# openSX70_LENS_BELLOWS_V5_5-SEEED_2018051.net
KiCad netlist of a schematic drawn in EAGLE
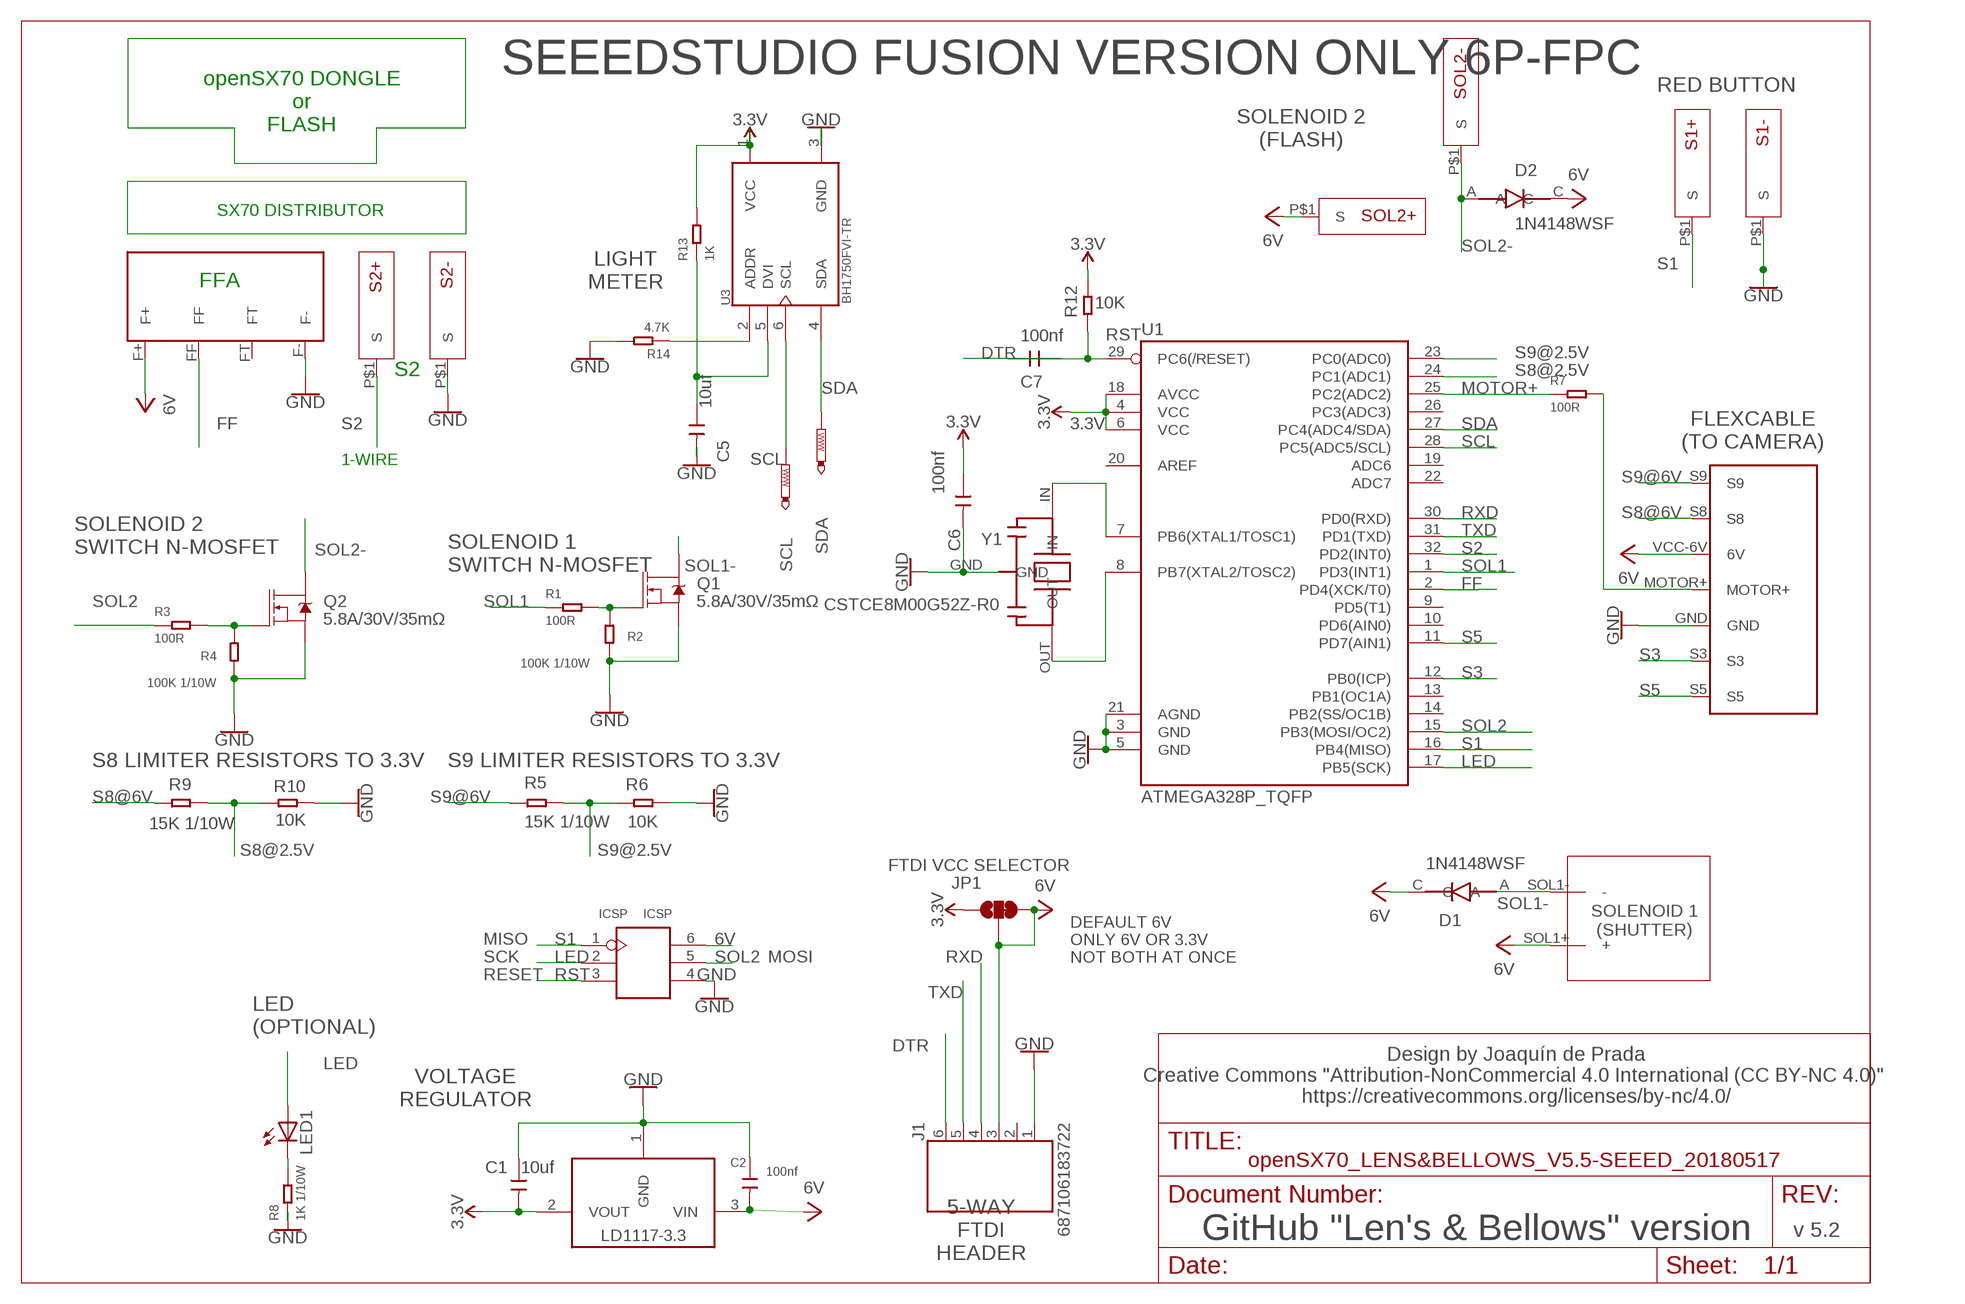
[diagram p0: schematic, sheet 1]

(export (version "E")
  (design (tool "Eeschema 10.0.6"))
  (components
    (comp (ref "C1")
      (value "10uf")
      (footprint "eagle-import:C0603")
      (fields (field (name "MPN") "CC0603KRX5R6BB106"))
      (libsource (lib "eagle-import") (part "CERAMIC-10UF-10V-10%-X5R(0603)"))
    )
    (comp (ref "C2")
      (value "100nf")
      (footprint "eagle-import:C0603")
      (fields (field (name "MPN") "CC0603KRX7R9BB104"))
      (libsource (lib "eagle-import") (part "CERAMIC-100NF-50V-10%-X7R(0603)"))
    )
    (comp (ref "C5")
      (value "10uf")
      (footprint "eagle-import:C0603")
      (fields (field (name "MPN") "CC0603KRX5R6BB106"))
      (libsource (lib "eagle-import") (part "CERAMIC-10UF-10V-10%-X5R(0603)"))
    )
    (comp (ref "C6")
      (value "100nf")
      (footprint "eagle-import:C0603")
      (fields (field (name "MPN") "CC0603KRX7R9BB104"))
      (libsource (lib "eagle-import") (part "CERAMIC-100NF-50V-10%-X7R(0603)"))
    )
    (comp (ref "C7")
      (value "100nf")
      (footprint "eagle-import:C0603")
      (fields (field (name "MPN") "CC0603KRX7R9BB104"))
      (libsource (lib "eagle-import") (part "CERAMIC-100NF-50V-10%-X7R(0603)"))
    )
    (comp (ref "D1")
      (value "1N4148WSF")
      (footprint "eagle-import:SODFL2512X100N")
      (fields (field (name "MANUFACTURER") "Fairchild Semiconductor"))
      (libsource (lib "eagle-import") (part "1N4148WS"))
    )
    (comp (ref "D2")
      (value "1N4148WSF")
      (footprint "eagle-import:SODFL2512X100N")
      (fields (field (name "MANUFACTURER") "Fairchild Semiconductor"))
      (libsource (lib "eagle-import") (part "1N4148WS"))
    )
    (comp (ref "ICSP")
      (value "ICSP")
      (footprint "eagle-import:H2X3-2.54")
      (libsource (lib "eagle-import") (part "ICSP"))
    )
    (comp (ref "J1")
      (value "687106183722")
      (footprint "eagle-import:687106183722")
      (fields (field (name "MF") "Wurth Electronics"))
      (libsource (lib "eagle-import") (part "687106183722"))
    )
    (comp (ref "JP1")
      (value "FTDI VCC SELECTOR")
      (footprint "eagle-import:SMT-JUMPER_3_1-NC_TRACE_SILK")
      (libsource (lib "eagle-import") (part "JUMPER-SMT_3_1-NC_TRACE_SILK"))
    )
    (comp (ref "LD11172.5V")
      (value "LD1117 2.5V")
      (footprint "eagle-import:SOT223")
      (fields (field (name "MF") "Advanced Monolithic Systems") (field (name "MP") "AMS1117-5.0"))
      (libsource (lib "eagle-import") (part "LD1117-3.3"))
    )
    (comp (ref "LED1")
      (value "LEDCHIPLED_0805")
      (footprint "eagle-import:CHIPLED_0805")
      (libsource (lib "eagle-import") (part "LEDCHIPLED_0805"))
    )
    (comp (ref "Q1")
      (value "5.8A/30V/35mΩ")
      (footprint "eagle-import:SOT23-3")
      (libsource (lib "eagle-import") (part "MOSFET-NCH-AO3404A"))
    )
    (comp (ref "Q2")
      (value "5.8A/30V/35mΩ")
      (footprint "eagle-import:SOT23-3")
      (libsource (lib "eagle-import") (part "MOSFET-NCH-AO3404A"))
    )
    (comp (ref "R1")
      (value "100R")
      (footprint "eagle-import:R0603")
      (fields (field (name "MPN") "RC0603JR-07100RL"))
      (libsource (lib "eagle-import") (part "SMD-RES-100R-5%-1/10W(0603)"))
    )
    (comp (ref "R2")
      (value "100K 1/10W")
      (footprint "eagle-import:R0603")
      (fields (field (name "MPN") "RC0603JR-07100KL"))
      (libsource (lib "eagle-import") (part "SMD-RES-100K-5%-1/10W(0603)"))
    )
    (comp (ref "R3")
      (value "100R")
      (footprint "eagle-import:R0603")
      (fields (field (name "MPN") "RC0603JR-07100RL"))
      (libsource (lib "eagle-import") (part "SMD-RES-100R-5%-1/10W(0603)"))
    )
    (comp (ref "R4")
      (value "100K 1/10W")
      (footprint "eagle-import:R0603")
      (fields (field (name "MPN") "RC0603JR-07100KL"))
      (libsource (lib "eagle-import") (part "SMD-RES-100K-5%-1/10W(0603)"))
    )
    (comp (ref "R5")
      (value "15K 1/10W")
      (footprint "eagle-import:R0603")
      (fields (field (name "MPN") "RC0603FR-0715KL"))
      (libsource (lib "eagle-import") (part "SMD-RES-15K-1%-1/10W(0603)"))
    )
    (comp (ref "R6")
      (value "10K")
      (footprint "eagle-import:R0603")
      (fields (field (name "MPN") "RC0603FR-0710KL"))
      (libsource (lib "eagle-import") (part "SMD-RES-10K-1%-1/10W(0603)"))
    )
    (comp (ref "R7")
      (value "100R")
      (footprint "eagle-import:R0603")
      (fields (field (name "MPN") "RC0603JR-07100RL"))
      (libsource (lib "eagle-import") (part "SMD-RES-100R-5%-1/10W(0603)"))
    )
    (comp (ref "R8")
      (value "1K 1/10W")
      (footprint "eagle-import:R0603")
      (fields (field (name "MPN") "RC0603JR-071KL"))
      (libsource (lib "eagle-import") (part "SMD-RES-1K-5%-1/10W(0603)"))
    )
    (comp (ref "R9")
      (value "15K 1/10W")
      (footprint "eagle-import:R0603")
      (fields (field (name "MPN") "RC0603FR-0715KL"))
      (libsource (lib "eagle-import") (part "SMD-RES-15K-1%-1/10W(0603)"))
    )
    (comp (ref "R10")
      (value "10K")
      (footprint "eagle-import:R0603")
      (fields (field (name "MPN") "RC0603FR-0710KL"))
      (libsource (lib "eagle-import") (part "SMD-RES-10K-1%-1/10W(0603)"))
    )
    (comp (ref "R12")
      (value "10K")
      (footprint "eagle-import:R0603")
      (fields (field (name "MPN") "RC0603FR-0710KL"))
      (libsource (lib "eagle-import") (part "SMD-RES-10K-1%-1/10W(0603)"))
    )
    (comp (ref "R13")
      (value "1K")
      (footprint "eagle-import:R0603")
      (fields (field (name "MPN") "RC0603FR-071KL"))
      (libsource (lib "eagle-import") (part "SMD-RES-1K-1%-1/10W(0603)"))
    )
    (comp (ref "R14")
      (value "4.7K")
      (footprint "eagle-import:R0603")
      (fields (field (name "MPN") "RC0603JR-074K7L"))
      (libsource (lib "eagle-import") (part "SMD-RES-4.7K-5%-1/10W(0603)"))
    )
    (comp (ref "S1+")
      (value "SX70-S-PAD-NEW")
      (footprint "eagle-import:SX70-S-PAD2")
      (libsource (lib "eagle-import") (part "SX70-S-PAD-NEW"))
    )
    (comp (ref "S1-")
      (value "SX70-S-PAD-NEW")
      (footprint "eagle-import:SX70-S-PAD2")
      (libsource (lib "eagle-import") (part "SX70-S-PAD-NEW"))
    )
    (comp (ref "S2+")
      (value "SX70-S-PAD-NEW")
      (footprint "eagle-import:SX70-S-PAD2")
      (libsource (lib "eagle-import") (part "SX70-S-PAD-NEW"))
    )
    (comp (ref "S2-")
      (value "SX70-S-PAD-NEW")
      (footprint "eagle-import:SX70-S-PAD2")
      (libsource (lib "eagle-import") (part "SX70-S-PAD-NEW"))
    )
    (comp (ref "SCL")
      (value "PTR1TP08R")
      (footprint "eagle-import:TP08R")
      (libsource (lib "eagle-import") (part "PTR1TP08R"))
    )
    (comp (ref "SDA")
      (value "PTR1TP08R")
      (footprint "eagle-import:TP08R")
      (libsource (lib "eagle-import") (part "PTR1TP08R"))
    )
    (comp (ref "SOL1")
      (value "SX70-SOLENOID1-2PADS")
      (footprint "eagle-import:SX70-SOLENOID1-2")
      (libsource (lib "eagle-import") (part "SX70-SOLENOID1-2PADS"))
    )
    (comp (ref "SOL2+")
      (value "SX70-S-PAD-NEW")
      (footprint "eagle-import:SX70-S-PAD2")
      (libsource (lib "eagle-import") (part "SX70-S-PAD-NEW"))
    )
    (comp (ref "SOL2-")
      (value "SX70-S-PAD-NEW")
      (footprint "eagle-import:SX70-S-PAD2")
      (libsource (lib "eagle-import") (part "SX70-S-PAD-NEW"))
    )
    (comp (ref "U$1")
      (value "SX70-7-PAD")
      (footprint "eagle-import:SX70-7-PAD")
      (libsource (lib "eagle-import") (part "SX70-7-PAD"))
    )
    (comp (ref "U$2")
      (value "FFA")
      (footprint "eagle-import:FFA-PAD-PACKAGE")
      (libsource (lib "eagle-import") (part "SX70-FFA-PAD"))
    )
    (comp (ref "U1")
      (value "ATMEGA328P_TQFP")
      (footprint "eagle-import:TQFP32-08")
      (libsource (lib "eagle-import") (part "ATMEGA328P_TQFP"))
    )
    (comp (ref "U3")
      (value "BH1750FVI-TR")
      (footprint "eagle-import:SOTFL50P300X75-6N")
      (fields (field (name "MF") "Rohm"))
      (libsource (lib "eagle-import") (part "BH1750FVI-TR"))
    )
    (comp (ref "Y1")
      (value "CSTCE8M00G52Z-R0")
      (footprint "eagle-import:CFP95P160X100-3N")
      (fields (field (name "MF") "Murata") (field (name "MP") "CSTCE16M0V53-R0"))
      (libsource (lib "eagle-import") (part "CSTCE16M0V53-R0"))
    )
  )
  (nets
    (net (code "1") (name "/DTR") (class "Default")
      (node (ref "C7") (pin "1") (pinfunction "1_1") (pintype "passive"))
      (node (ref "J1") (pin "6") (pinfunction "1_6") (pintype "passive"))
    )
    (net (code "2") (name "/FF") (class "Default")
      (node (ref "U$2") (pin "FF") (pinfunction "FF_FF") (pintype "bidirectional"))
      (node (ref "U1") (pin "2") (pinfunction "PD4(XCK/T0)_2") (pintype "bidirectional"))
    )
    (net (code "3") (name "/LED") (class "Default")
      (node (ref "ICSP") (pin "2") (pinfunction "SCK_2") (pintype "bidirectional"))
      (node (ref "LED1") (pin "A") (pinfunction "A_A") (pintype "passive"))
      (node (ref "U1") (pin "17") (pinfunction "PB5(SCK)_17") (pintype "bidirectional"))
    )
    (net (code "4") (name "/MOTOR+") (class "Default")
      (node (ref "R7") (pin "1") (pinfunction "1_1") (pintype "passive"))
      (node (ref "U1") (pin "25") (pinfunction "PC2(ADC2)_25") (pintype "bidirectional"))
    )
    (net (code "5") (name "/RST") (class "Default")
      (node (ref "C7") (pin "2") (pinfunction "2_2") (pintype "passive"))
      (node (ref "ICSP") (pin "3") (pinfunction "RST_3") (pintype "bidirectional"))
      (node (ref "R12") (pin "1") (pinfunction "1_1") (pintype "passive"))
      (node (ref "U1") (pin "29") (pinfunction "PC6(/RESET)_29") (pintype "bidirectional"))
    )
    (net (code "6") (name "/RXD") (class "Default")
      (node (ref "J1") (pin "4") (pinfunction "3_4") (pintype "passive"))
      (node (ref "U1") (pin "30") (pinfunction "PD0(RXD)_30") (pintype "bidirectional"))
    )
    (net (code "7") (name "/S1") (class "Default")
      (node (ref "ICSP") (pin "1") (pinfunction "MISO_1") (pintype "bidirectional"))
      (node (ref "S1+") (pin "P$1") (pinfunction "S_P$1") (pintype "bidirectional"))
      (node (ref "U1") (pin "16") (pinfunction "PB4(MISO)_16") (pintype "bidirectional"))
    )
    (net (code "8") (name "/S2") (class "Default")
      (node (ref "S2+") (pin "P$1") (pinfunction "S_P$1") (pintype "bidirectional"))
      (node (ref "U1") (pin "32") (pinfunction "PD2(INT0)_32") (pintype "bidirectional"))
    )
    (net (code "9") (name "/S3") (class "Default")
      (node (ref "U$1") (pin "S3") (pinfunction "S3_S3") (pintype "bidirectional"))
      (node (ref "U1") (pin "12") (pinfunction "PB0(ICP)_12") (pintype "bidirectional"))
    )
    (net (code "10") (name "/S5") (class "Default")
      (node (ref "U$1") (pin "S5") (pinfunction "S5_S5") (pintype "bidirectional"))
      (node (ref "U1") (pin "11") (pinfunction "PD7(AIN1)_11") (pintype "bidirectional"))
    )
    (net (code "11") (name "/S8@2.5V") (class "Default")
      (node (ref "R10") (pin "1") (pinfunction "1_1") (pintype "passive"))
      (node (ref "R9") (pin "2") (pinfunction "2_2") (pintype "passive"))
      (node (ref "U1") (pin "24") (pinfunction "PC1(ADC1)_24") (pintype "bidirectional"))
    )
    (net (code "12") (name "/S8@6V") (class "Default")
      (node (ref "R9") (pin "1") (pinfunction "1_1") (pintype "passive"))
      (node (ref "U$1") (pin "S8") (pinfunction "S8_S8") (pintype "bidirectional"))
    )
    (net (code "13") (name "/S9@2.5V") (class "Default")
      (node (ref "R5") (pin "2") (pinfunction "2_2") (pintype "passive"))
      (node (ref "R6") (pin "1") (pinfunction "1_1") (pintype "passive"))
      (node (ref "U1") (pin "23") (pinfunction "PC0(ADC0)_23") (pintype "bidirectional"))
    )
    (net (code "14") (name "/S9@6V") (class "Default")
      (node (ref "R5") (pin "1") (pinfunction "1_1") (pintype "passive"))
      (node (ref "U$1") (pin "S9") (pinfunction "S9_S9") (pintype "bidirectional"))
    )
    (net (code "15") (name "/SCL") (class "Default")
      (node (ref "SCL") (pin "TP") (pinfunction "TP_TP") (pintype "input"))
      (node (ref "U1") (pin "28") (pinfunction "PC5(ADC5/SCL)_28") (pintype "bidirectional"))
      (node (ref "U3") (pin "6") (pinfunction "SCL_6") (pintype "input"))
    )
    (net (code "16") (name "/SDA") (class "Default")
      (node (ref "SDA") (pin "TP") (pinfunction "TP_TP") (pintype "input"))
      (node (ref "U1") (pin "27") (pinfunction "PC4(ADC4/SDA)_27") (pintype "bidirectional"))
      (node (ref "U3") (pin "4") (pinfunction "SDA_4") (pintype "bidirectional"))
    )
    (net (code "17") (name "/SOL1") (class "Default")
      (node (ref "R1") (pin "1") (pinfunction "1_1") (pintype "passive"))
      (node (ref "U1") (pin "1") (pinfunction "PD3(INT1)_1") (pintype "bidirectional"))
    )
    (net (code "18") (name "/SOL1-") (class "Default")
      (node (ref "D1") (pin "A") (pinfunction "A_A") (pintype "passive"))
      (node (ref "Q1") (pin "3") (pinfunction "D_3") (pintype "bidirectional"))
      (node (ref "SOL1") (pin "SOL1-") (pinfunction "-_SOL1-") (pintype "bidirectional"))
    )
    (net (code "19") (name "/SOL2") (class "Default")
      (node (ref "ICSP") (pin "5") (pinfunction "MOSI_5") (pintype "bidirectional"))
      (node (ref "R3") (pin "1") (pinfunction "1_1") (pintype "passive"))
      (node (ref "U1") (pin "15") (pinfunction "PB3(MOSI/OC2)_15") (pintype "bidirectional"))
    )
    (net (code "20") (name "/SOL2-") (class "Default")
      (node (ref "D2") (pin "A") (pinfunction "A_A") (pintype "passive"))
      (node (ref "Q2") (pin "3") (pinfunction "D_3") (pintype "bidirectional"))
      (node (ref "SOL2-") (pin "P$1") (pinfunction "S_P$1") (pintype "bidirectional"))
    )
    (net (code "21") (name "/TXD") (class "Default")
      (node (ref "J1") (pin "5") (pinfunction "2_5") (pintype "passive"))
      (node (ref "U1") (pin "31") (pinfunction "PD1(TXD)_31") (pintype "bidirectional"))
    )
    (net (code "22") (name "3.3V") (class "Default")
      (node (ref "C1") (pin "2") (pinfunction "2_2") (pintype "passive"))
      (node (ref "C6") (pin "1") (pinfunction "1_1") (pintype "passive"))
      (node (ref "JP1") (pin "1") (pinfunction "1_1") (pintype "passive"))
      (node (ref "LD11172.5V") (pin "2") (pinfunction "VOUT_2") (pintype "bidirectional"))
      (node (ref "R12") (pin "2") (pinfunction "2_2") (pintype "passive"))
      (node (ref "R13") (pin "2") (pinfunction "2_2") (pintype "passive"))
      (node (ref "U1") (pin "18") (pinfunction "AVCC_18") (pintype "bidirectional"))
      (node (ref "U1") (pin "4") (pinfunction "VCC_4") (pintype "bidirectional"))
      (node (ref "U1") (pin "6") (pinfunction "VCC_6") (pintype "bidirectional"))
      (node (ref "U3") (pin "1") (pinfunction "VCC_1") (pintype "power_in"))
    )
    (net (code "23") (name "6V") (class "Default")
      (node (ref "C2") (pin "2") (pinfunction "2_2") (pintype "passive"))
      (node (ref "D1") (pin "C") (pinfunction "C_C") (pintype "passive"))
      (node (ref "D2") (pin "C") (pinfunction "C_C") (pintype "passive"))
      (node (ref "ICSP") (pin "6") (pinfunction "VCC_6") (pintype "bidirectional"))
      (node (ref "J1") (pin "3") (pinfunction "4_3") (pintype "passive"))
      (node (ref "JP1") (pin "2") (pinfunction "2_2") (pintype "passive"))
      (node (ref "JP1") (pin "3") (pinfunction "3_3") (pintype "passive"))
      (node (ref "LD11172.5V") (pin "3") (pinfunction "VIN_3") (pintype "bidirectional"))
      (node (ref "SOL1") (pin "SOL1+") (pinfunction "+_SOL1+") (pintype "bidirectional"))
      (node (ref "SOL2+") (pin "P$1") (pinfunction "S_P$1") (pintype "bidirectional"))
      (node (ref "U$1") (pin "VCC-6V") (pinfunction "6V_VCC-6V") (pintype "bidirectional"))
      (node (ref "U$2") (pin "F+") (pinfunction "F+_F+") (pintype "bidirectional"))
    )
    (net (code "24") (name "GND") (class "Default")
      (node (ref "C1") (pin "1") (pinfunction "1_1") (pintype "passive"))
      (node (ref "C2") (pin "1") (pinfunction "1_1") (pintype "passive"))
      (node (ref "C5") (pin "2") (pinfunction "2_2") (pintype "passive"))
      (node (ref "C6") (pin "2") (pinfunction "2_2") (pintype "passive"))
      (node (ref "ICSP") (pin "4") (pinfunction "GND_4") (pintype "bidirectional"))
      (node (ref "J1") (pin "1") (pinfunction "6_1") (pintype "passive"))
      (node (ref "LD11172.5V") (pin "1") (pinfunction "GND_1") (pintype "bidirectional"))
      (node (ref "Q1") (pin "2") (pinfunction "S_2") (pintype "bidirectional"))
      (node (ref "Q2") (pin "2") (pinfunction "S_2") (pintype "bidirectional"))
      (node (ref "R10") (pin "2") (pinfunction "2_2") (pintype "passive"))
      (node (ref "R14") (pin "2") (pinfunction "2_2") (pintype "passive"))
      (node (ref "R2") (pin "1") (pinfunction "1_1") (pintype "passive"))
      (node (ref "R4") (pin "1") (pinfunction "1_1") (pintype "passive"))
      (node (ref "R6") (pin "2") (pinfunction "2_2") (pintype "passive"))
      (node (ref "R8") (pin "1") (pinfunction "1_1") (pintype "passive"))
      (node (ref "S1-") (pin "P$1") (pinfunction "S_P$1") (pintype "bidirectional"))
      (node (ref "S2-") (pin "P$1") (pinfunction "S_P$1") (pintype "bidirectional"))
      (node (ref "U$1") (pin "GND") (pinfunction "GND_GND") (pintype "bidirectional"))
      (node (ref "U$2") (pin "F-") (pinfunction "F-_F-") (pintype "bidirectional"))
      (node (ref "U1") (pin "21") (pinfunction "AGND_21") (pintype "bidirectional"))
      (node (ref "U1") (pin "3") (pinfunction "GND_3") (pintype "bidirectional"))
      (node (ref "U1") (pin "5") (pinfunction "GND_5") (pintype "bidirectional"))
      (node (ref "U3") (pin "3") (pinfunction "GND_3") (pintype "power_in"))
      (node (ref "Y1") (pin "GND") (pinfunction "GND_GND") (pintype "passive"))
    )
    (net (code "25") (name "Net-(LED1-PadC)") (class "Default")
      (node (ref "LED1") (pin "C") (pinfunction "C_C") (pintype "passive"))
      (node (ref "R8") (pin "2") (pinfunction "2_2") (pintype "passive"))
    )
    (net (code "26") (name "Net-(Q1-G)") (class "Default")
      (node (ref "Q1") (pin "1") (pinfunction "G_1") (pintype "bidirectional"))
      (node (ref "R1") (pin "2") (pinfunction "2_2") (pintype "passive"))
      (node (ref "R2") (pin "2") (pinfunction "2_2") (pintype "passive"))
    )
    (net (code "27") (name "Net-(Q2-G)") (class "Default")
      (node (ref "Q2") (pin "1") (pinfunction "G_1") (pintype "bidirectional"))
      (node (ref "R3") (pin "2") (pinfunction "2_2") (pintype "passive"))
      (node (ref "R4") (pin "2") (pinfunction "2_2") (pintype "passive"))
    )
    (net (code "28") (name "Net-(R7-Pad2)") (class "Default")
      (node (ref "R7") (pin "2") (pinfunction "2_2") (pintype "passive"))
      (node (ref "U$1") (pin "MOTOR+") (pinfunction "MOTOR+_MOTOR+") (pintype "bidirectional"))
    )
    (net (code "29") (name "Net-(U1-PB6(XTAL1{slash}TOSC1))") (class "Default")
      (node (ref "U1") (pin "7") (pinfunction "PB6(XTAL1/TOSC1)_7") (pintype "bidirectional"))
      (node (ref "Y1") (pin "IN") (pinfunction "IN_IN") (pintype "input"))
    )
    (net (code "30") (name "Net-(U1-PB7(XTAL2{slash}TOSC2))") (class "Default")
      (node (ref "U1") (pin "8") (pinfunction "PB7(XTAL2/TOSC2)_8") (pintype "bidirectional"))
      (node (ref "Y1") (pin "OUT") (pinfunction "OUT_OUT") (pintype "output"))
    )
    (net (code "31") (name "Net-(U3-ADDR)") (class "Default")
      (node (ref "R14") (pin "1") (pinfunction "1_1") (pintype "passive"))
      (node (ref "U3") (pin "2") (pinfunction "ADDR_2") (pintype "input"))
    )
    (net (code "32") (name "Net-(U3-DVI)") (class "Default")
      (node (ref "C5") (pin "1") (pinfunction "1_1") (pintype "passive"))
      (node (ref "R13") (pin "1") (pinfunction "1_1") (pintype "passive"))
      (node (ref "U3") (pin "5") (pinfunction "DVI_5") (pintype "input"))
    )
    (net (code "33") (name "unconnected-(J1-5-Pad2)") (class "Default")
      (node (ref "J1") (pin "2") (pinfunction "5_2") (pintype "passive"))
    )
    (net (code "34") (name "unconnected-(U$2-PadFT)") (class "Default")
      (node (ref "U$2") (pin "FT") (pinfunction "FT_FT") (pintype "bidirectional"))
    )
    (net (code "35") (name "unconnected-(U1-ADC6-Pad19)") (class "Default")
      (node (ref "U1") (pin "19") (pinfunction "ADC6_19") (pintype "bidirectional"))
    )
    (net (code "36") (name "unconnected-(U1-ADC7-Pad22)") (class "Default")
      (node (ref "U1") (pin "22") (pinfunction "ADC7_22") (pintype "bidirectional"))
    )
    (net (code "37") (name "unconnected-(U1-AREF-Pad20)") (class "Default")
      (node (ref "U1") (pin "20") (pinfunction "AREF_20") (pintype "bidirectional"))
    )
    (net (code "38") (name "unconnected-(U1-PB1(OC1A)-Pad13)") (class "Default")
      (node (ref "U1") (pin "13") (pinfunction "PB1(OC1A)_13") (pintype "bidirectional"))
    )
    (net (code "39") (name "unconnected-(U1-PB2(SS{slash}OC1B)-Pad14)") (class "Default")
      (node (ref "U1") (pin "14") (pinfunction "PB2(SS/OC1B)_14") (pintype "bidirectional"))
    )
    (net (code "40") (name "unconnected-(U1-PC3(ADC3)-Pad26)") (class "Default")
      (node (ref "U1") (pin "26") (pinfunction "PC3(ADC3)_26") (pintype "bidirectional"))
    )
    (net (code "41") (name "unconnected-(U1-PD5(T1)-Pad9)") (class "Default")
      (node (ref "U1") (pin "9") (pinfunction "PD5(T1)_9") (pintype "bidirectional"))
    )
    (net (code "42") (name "unconnected-(U1-PD6(AIN0)-Pad10)") (class "Default")
      (node (ref "U1") (pin "10") (pinfunction "PD6(AIN0)_10") (pintype "bidirectional"))
    )
  )
)
